# SerialTerminations.net
KiCad netlist of a schematic drawn in Altium Designer
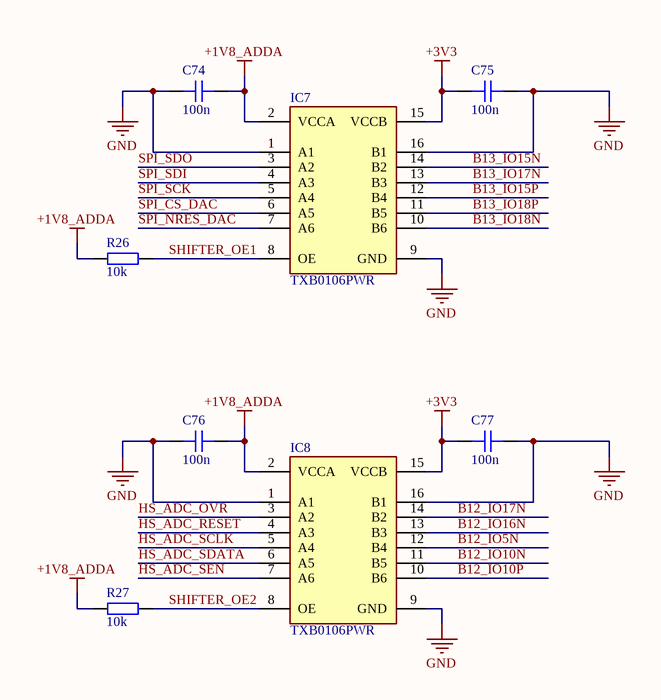
[diagram p0: SerialTerminations.SchDoc]

(export (version "E")
  (design (tool "Eeschema 10.0.6"))
  (components
    (comp (ref "C74")
      (value "100n")
      (footprint "CAP_0402")
      (description "Capacitor SMD 0402")
      (libsource (lib "Schematic-Lib-PhilsLab") (part "CAP_0402"))
    )
    (comp (ref "C75")
      (value "100n")
      (footprint "CAP_0402")
      (description "Capacitor SMD 0402")
      (libsource (lib "Schematic-Lib-PhilsLab") (part "CAP_0402"))
    )
    (comp (ref "C76")
      (value "100n")
      (footprint "CAP_0402")
      (description "Capacitor SMD 0402")
      (libsource (lib "Schematic-Lib-PhilsLab") (part "CAP_0402"))
    )
    (comp (ref "C77")
      (value "100n")
      (footprint "CAP_0402")
      (description "Capacitor SMD 0402")
      (libsource (lib "Schematic-Lib-PhilsLab") (part "CAP_0402"))
    )
    (comp (ref "IC7")
      (value "TXB0106PWR")
      (footprint "XC7Z030PCBLib:SOP65P640X120-16N")
      (description "Integrated Circuit")
      (fields (field (name "MOUSER PART NUMBER") "595-TXB0106PWR"))
      (libsource (lib "XC7Z030SCHLib") (part "TXB0106PWR"))
    )
    (comp (ref "IC8")
      (value "TXB0106PWR")
      (footprint "XC7Z030PCBLib:SOP65P640X120-16N")
      (description "Integrated Circuit")
      (fields (field (name "MOUSER PART NUMBER") "595-TXB0106PWR"))
      (libsource (lib "XC7Z030SCHLib") (part "TXB0106PWR"))
    )
    (comp (ref "R26")
      (value "10k")
      (footprint "RES_0402")
      (description "Resistor SMD 0402")
      (libsource (lib "Schematic-Lib-PhilsLab") (part "RES_0402"))
    )
    (comp (ref "R27")
      (value "10k")
      (footprint "RES_0402")
      (description "Resistor SMD 0402")
      (libsource (lib "Schematic-Lib-PhilsLab") (part "RES_0402"))
    )
  )
  (nets
    (net (code "1") (name "+1V8_ADDA") (class "Default")
      (node (ref "C74") (pin "2") (pinfunction "2_2") (pintype "passive"))
      (node (ref "C76") (pin "2") (pinfunction "2_2") (pintype "passive"))
      (node (ref "IC7") (pin "2") (pinfunction "VCCA_2") (pintype "passive"))
      (node (ref "IC8") (pin "2") (pinfunction "VCCA_2") (pintype "passive"))
      (node (ref "R26") (pin "1") (pinfunction "1_1") (pintype "passive"))
      (node (ref "R27") (pin "1") (pinfunction "1_1") (pintype "passive"))
    )
    (net (code "2") (name "+3V3") (class "Default")
      (node (ref "C75") (pin "1") (pinfunction "1_1") (pintype "passive"))
      (node (ref "C77") (pin "1") (pinfunction "1_1") (pintype "passive"))
      (node (ref "IC7") (pin "15") (pinfunction "VCCB_15") (pintype "passive"))
      (node (ref "IC8") (pin "15") (pinfunction "VCCB_15") (pintype "passive"))
    )
    (net (code "3") (name "/B12_IO5N") (class "Default")
      (node (ref "IC8") (pin "12") (pinfunction "B4_12") (pintype "passive"))
    )
    (net (code "4") (name "/B12_IO10N") (class "Default")
      (node (ref "IC8") (pin "11") (pinfunction "B5_11") (pintype "passive"))
    )
    (net (code "5") (name "/B12_IO10P") (class "Default")
      (node (ref "IC8") (pin "10") (pinfunction "B6_10") (pintype "passive"))
    )
    (net (code "6") (name "/B12_IO16N") (class "Default")
      (node (ref "IC8") (pin "13") (pinfunction "B3_13") (pintype "passive"))
    )
    (net (code "7") (name "/B12_IO17N") (class "Default")
      (node (ref "IC8") (pin "14") (pinfunction "B2_14") (pintype "passive"))
    )
    (net (code "8") (name "/B13_IO15N") (class "Default")
      (node (ref "IC7") (pin "14") (pinfunction "B2_14") (pintype "passive"))
    )
    (net (code "9") (name "/B13_IO15P") (class "Default")
      (node (ref "IC7") (pin "12") (pinfunction "B4_12") (pintype "passive"))
    )
    (net (code "10") (name "/B13_IO17N") (class "Default")
      (node (ref "IC7") (pin "13") (pinfunction "B3_13") (pintype "passive"))
    )
    (net (code "11") (name "/B13_IO18N") (class "Default")
      (node (ref "IC7") (pin "10") (pinfunction "B6_10") (pintype "passive"))
    )
    (net (code "12") (name "/B13_IO18P") (class "Default")
      (node (ref "IC7") (pin "11") (pinfunction "B5_11") (pintype "passive"))
    )
    (net (code "13") (name "/HS_ADC_OVR") (class "Default")
      (node (ref "IC8") (pin "3") (pinfunction "A2_3") (pintype "passive"))
    )
    (net (code "14") (name "/HS_ADC_RESET") (class "Default")
      (node (ref "IC8") (pin "4") (pinfunction "A3_4") (pintype "passive"))
    )
    (net (code "15") (name "/HS_ADC_SCLK") (class "Default")
      (node (ref "IC8") (pin "5") (pinfunction "A4_5") (pintype "passive"))
    )
    (net (code "16") (name "/HS_ADC_SDATA") (class "Default")
      (node (ref "IC8") (pin "6") (pinfunction "A5_6") (pintype "passive"))
    )
    (net (code "17") (name "/HS_ADC_SEN") (class "Default")
      (node (ref "IC8") (pin "7") (pinfunction "A6_7") (pintype "passive"))
    )
    (net (code "18") (name "/SHIFTER_OE1") (class "Default")
      (node (ref "IC7") (pin "8") (pinfunction "OE_8") (pintype "passive"))
      (node (ref "R26") (pin "2") (pinfunction "2_2") (pintype "passive"))
    )
    (net (code "19") (name "/SHIFTER_OE2") (class "Default")
      (node (ref "IC8") (pin "8") (pinfunction "OE_8") (pintype "passive"))
      (node (ref "R27") (pin "2") (pinfunction "2_2") (pintype "passive"))
    )
    (net (code "20") (name "/SPI_CS_DAC") (class "Default")
      (node (ref "IC7") (pin "6") (pinfunction "A5_6") (pintype "passive"))
    )
    (net (code "21") (name "/SPI_NRES_DAC") (class "Default")
      (node (ref "IC7") (pin "7") (pinfunction "A6_7") (pintype "passive"))
    )
    (net (code "22") (name "/SPI_SCK") (class "Default")
      (node (ref "IC7") (pin "5") (pinfunction "A4_5") (pintype "passive"))
    )
    (net (code "23") (name "/SPI_SDI") (class "Default")
      (node (ref "IC7") (pin "4") (pinfunction "A3_4") (pintype "passive"))
    )
    (net (code "24") (name "/SPI_SDO") (class "Default")
      (node (ref "IC7") (pin "3") (pinfunction "A2_3") (pintype "passive"))
    )
    (net (code "25") (name "GND") (class "Default")
      (node (ref "C74") (pin "1") (pinfunction "1_1") (pintype "passive"))
      (node (ref "C75") (pin "2") (pinfunction "2_2") (pintype "passive"))
      (node (ref "C76") (pin "1") (pinfunction "1_1") (pintype "passive"))
      (node (ref "C77") (pin "2") (pinfunction "2_2") (pintype "passive"))
      (node (ref "IC7") (pin "1") (pinfunction "A1_1") (pintype "passive"))
      (node (ref "IC7") (pin "16") (pinfunction "B1_16") (pintype "passive"))
      (node (ref "IC7") (pin "9") (pinfunction "GND_9") (pintype "passive"))
      (node (ref "IC8") (pin "1") (pinfunction "A1_1") (pintype "passive"))
      (node (ref "IC8") (pin "16") (pinfunction "B1_16") (pintype "passive"))
      (node (ref "IC8") (pin "9") (pinfunction "GND_9") (pintype "passive"))
    )
  )
)
